# USBReallyTinyISPv1.net
KiCad netlist of a schematic drawn in EAGLE
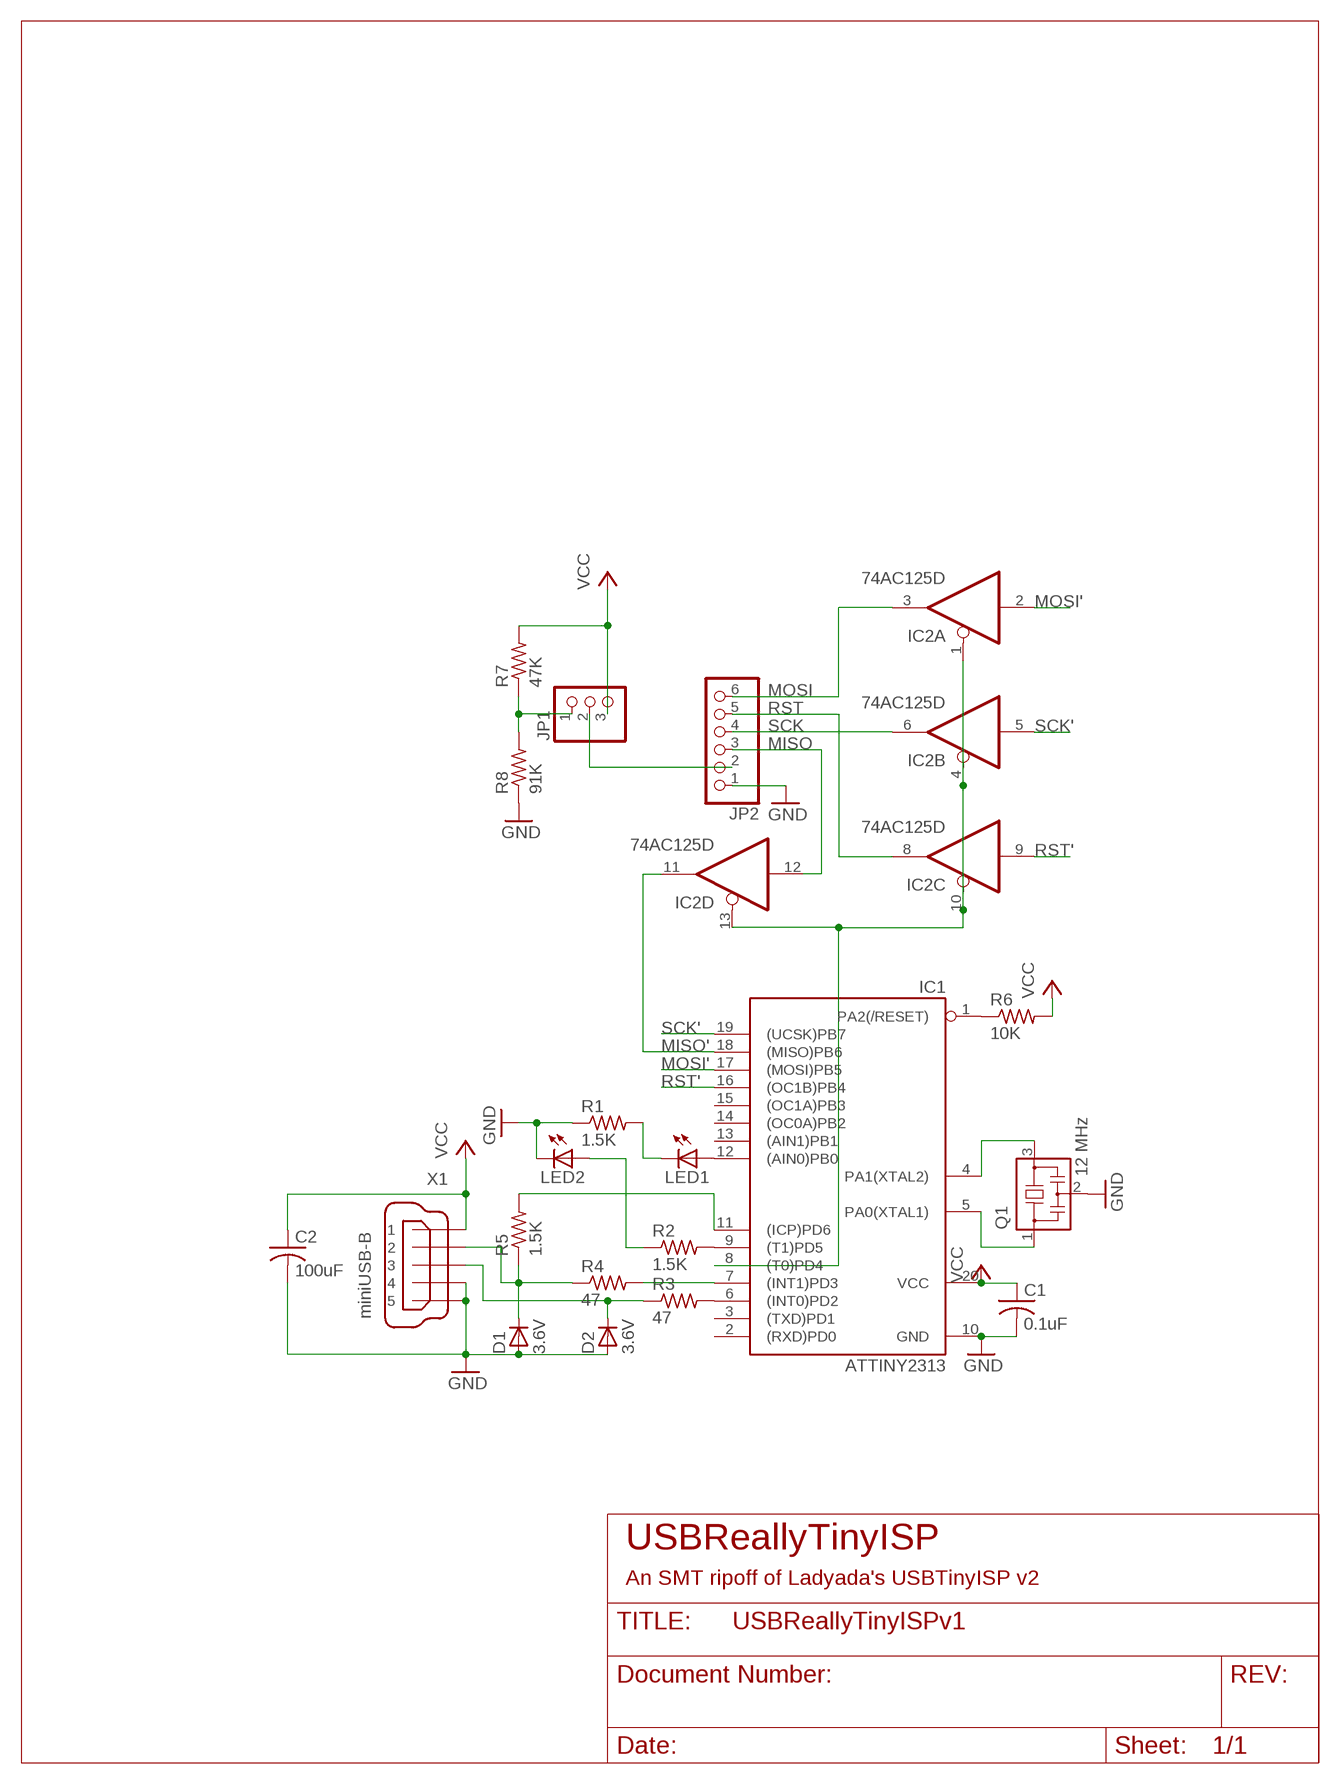
[diagram p0: schematic, sheet 1]

(export (version "E")
  (design (tool "Eeschema 10.0.6"))
  (components
    (comp (ref "C1")
      (value "0.1uF")
      (footprint "eagle-import:C0805")
      (libsource (lib "eagle-import") (part "C-USC0805"))
    )
    (comp (ref "C2")
      (value "100uF")
      (footprint "eagle-import:C1206")
      (libsource (lib "eagle-import") (part "resistor_C-USC1206"))
    )
    (comp (ref "D1")
      (value "3.6V")
      (footprint "eagle-import:SOD3718X135N")
      (libsource (lib "eagle-import") (part "DIODE_SOD-123"))
    )
    (comp (ref "D2")
      (value "3.6V")
      (footprint "eagle-import:SOD3718X135N")
      (libsource (lib "eagle-import") (part "DIODE_SOD-123"))
    )
    (comp (ref "IC1")
      (value "ATTINY2313")
      (footprint "eagle-import:SO20L$")
      (libsource (lib "eagle-import") (part "TINY2313-S"))
    )
    (comp (ref "IC2")
      (value "74AC125D")
      (footprint "eagle-import:SO14")
      (libsource (lib "eagle-import") (part "74125DAC"))
    )
    (comp (ref "JP1")
      (value "PINHD-1X3")
      (footprint "eagle-import:1X03")
      (libsource (lib "eagle-import") (part "PINHD-1X3"))
    )
    (comp (ref "JP2")
      (value "PINHD-1X6")
      (footprint "eagle-import:1X06")
      (libsource (lib "eagle-import") (part "PINHD-1X6"))
    )
    (comp (ref "LED1")
      (value "LEDSML0805")
      (footprint "eagle-import:SML0805")
      (libsource (lib "eagle-import") (part "LEDSML0805"))
    )
    (comp (ref "LED2")
      (value "LEDSML0805")
      (footprint "eagle-import:SML0805")
      (libsource (lib "eagle-import") (part "LEDSML0805"))
    )
    (comp (ref "Q1")
      (value "12 MHz")
      (footprint "eagle-import:CSTCR6M")
      (fields (field (name "MPN") "CSTCR6M00G53-R0"))
      (libsource (lib "eagle-import") (part "CSTCR6M00G53Z"))
    )
    (comp (ref "R1")
      (value "1.5K")
      (footprint "eagle-import:R0805")
      (libsource (lib "eagle-import") (part "R-US_R0805"))
    )
    (comp (ref "R2")
      (value "1.5K")
      (footprint "eagle-import:R0805")
      (libsource (lib "eagle-import") (part "R-US_R0805"))
    )
    (comp (ref "R3")
      (value "47")
      (footprint "eagle-import:R0805")
      (libsource (lib "eagle-import") (part "R-US_R0805"))
    )
    (comp (ref "R4")
      (value "47")
      (footprint "eagle-import:R0805")
      (libsource (lib "eagle-import") (part "R-US_R0805"))
    )
    (comp (ref "R5")
      (value "1.5K")
      (footprint "eagle-import:R0805")
      (libsource (lib "eagle-import") (part "R-US_R0805"))
    )
    (comp (ref "R6")
      (value "10K")
      (footprint "eagle-import:R0805")
      (libsource (lib "eagle-import") (part "R-US_R0805"))
    )
    (comp (ref "R7")
      (value "47K")
      (footprint "eagle-import:R0805")
      (libsource (lib "eagle-import") (part "R-US_R0805"))
    )
    (comp (ref "R8")
      (value "91K")
      (footprint "eagle-import:R0805")
      (libsource (lib "eagle-import") (part "R-US_R0805"))
    )
    (comp (ref "X1")
      (value "miniUSB-B")
      (footprint "eagle-import:UX60A-MB-5ST")
      (libsource (lib "eagle-import") (part "MINI-USB-UX60A-MB-5ST"))
    )
  )
  (nets
    (net (code "1") (name "/MISO") (class "Default")
      (node (ref "IC2") (pin "12") (pinfunction "I_12") (pintype "input"))
      (node (ref "JP2") (pin "3") (pinfunction "3_3") (pintype "passive"))
    )
    (net (code "2") (name "/MISO'") (class "Default")
      (node (ref "IC1") (pin "18") (pinfunction "(MISO)PB6_18") (pintype "bidirectional"))
      (node (ref "IC2") (pin "11") (pinfunction "O_11") (pintype "tri_state"))
    )
    (net (code "3") (name "/MOSI") (class "Default")
      (node (ref "IC2") (pin "3") (pinfunction "O_3") (pintype "tri_state"))
      (node (ref "JP2") (pin "6") (pinfunction "6_6") (pintype "passive"))
    )
    (net (code "4") (name "/MOSI'") (class "Default")
      (node (ref "IC1") (pin "17") (pinfunction "(MOSI)PB5_17") (pintype "bidirectional"))
      (node (ref "IC2") (pin "2") (pinfunction "I_2") (pintype "input"))
    )
    (net (code "5") (name "/RST") (class "Default")
      (node (ref "IC2") (pin "8") (pinfunction "O_8") (pintype "tri_state"))
      (node (ref "JP2") (pin "5") (pinfunction "5_5") (pintype "passive"))
    )
    (net (code "6") (name "/RST'") (class "Default")
      (node (ref "IC1") (pin "16") (pinfunction "(OC1B)PB4_16") (pintype "bidirectional"))
      (node (ref "IC2") (pin "9") (pinfunction "I_9") (pintype "input"))
    )
    (net (code "7") (name "/SCK") (class "Default")
      (node (ref "IC2") (pin "6") (pinfunction "O_6") (pintype "tri_state"))
      (node (ref "JP2") (pin "4") (pinfunction "4_4") (pintype "passive"))
    )
    (net (code "8") (name "/SCK'") (class "Default")
      (node (ref "IC1") (pin "19") (pinfunction "(UCSK)PB7_19") (pintype "bidirectional"))
      (node (ref "IC2") (pin "5") (pinfunction "I_5") (pintype "input"))
    )
    (net (code "9") (name "GND") (class "Default")
      (node (ref "C1") (pin "2") (pinfunction "2_2") (pintype "passive"))
      (node (ref "C2") (pin "2") (pinfunction "2_2") (pintype "passive"))
      (node (ref "D1") (pin "A") (pinfunction "A_A") (pintype "passive"))
      (node (ref "D2") (pin "A") (pinfunction "A_A") (pintype "passive"))
      (node (ref "IC1") (pin "10") (pinfunction "GND_10") (pintype "power_in"))
      (node (ref "JP2") (pin "1") (pinfunction "1_1") (pintype "passive"))
      (node (ref "LED2") (pin "C") (pinfunction "C_C") (pintype "passive"))
      (node (ref "Q1") (pin "2") (pinfunction "2_2") (pintype "passive"))
      (node (ref "R1") (pin "1") (pinfunction "1_1") (pintype "passive"))
      (node (ref "R8") (pin "1") (pinfunction "1_1") (pintype "passive"))
      (node (ref "X1") (pin "4") (pinfunction "4_4") (pintype "input"))
      (node (ref "X1") (pin "5") (pinfunction "5_5") (pintype "input"))
    )
    (net (code "10") (name "Net-(D1-PadK)") (class "Default")
      (node (ref "D1") (pin "K") (pinfunction "K_K") (pintype "passive"))
      (node (ref "R4") (pin "1") (pinfunction "1_1") (pintype "passive"))
      (node (ref "R5") (pin "1") (pinfunction "1_1") (pintype "passive"))
      (node (ref "X1") (pin "2") (pinfunction "2_2") (pintype "input"))
    )
    (net (code "11") (name "Net-(D2-PadK)") (class "Default")
      (node (ref "D2") (pin "K") (pinfunction "K_K") (pintype "passive"))
      (node (ref "R3") (pin "1") (pinfunction "1_1") (pintype "passive"))
      (node (ref "X1") (pin "3") (pinfunction "3_3") (pintype "input"))
    )
    (net (code "12") (name "Net-(IC1-(AIN0)PB0)") (class "Default")
      (node (ref "IC1") (pin "12") (pinfunction "(AIN0)PB0_12") (pintype "bidirectional"))
      (node (ref "LED1") (pin "A") (pinfunction "A_A") (pintype "passive"))
    )
    (net (code "13") (name "Net-(IC1-(ICP)PD6)") (class "Default")
      (node (ref "IC1") (pin "11") (pinfunction "(ICP)PD6_11") (pintype "bidirectional"))
      (node (ref "R5") (pin "2") (pinfunction "2_2") (pintype "passive"))
    )
    (net (code "14") (name "Net-(IC1-(INT0)PD2)") (class "Default")
      (node (ref "IC1") (pin "6") (pinfunction "(INT0)PD2_6") (pintype "bidirectional"))
      (node (ref "R3") (pin "2") (pinfunction "2_2") (pintype "passive"))
    )
    (net (code "15") (name "Net-(IC1-(INT1)PD3)") (class "Default")
      (node (ref "IC1") (pin "7") (pinfunction "(INT1)PD3_7") (pintype "bidirectional"))
      (node (ref "R4") (pin "2") (pinfunction "2_2") (pintype "passive"))
    )
    (net (code "16") (name "Net-(IC1-(T0)PD4)") (class "Default")
      (node (ref "IC1") (pin "8") (pinfunction "(T0)PD4_8") (pintype "bidirectional"))
      (node (ref "IC2") (pin "1") (pinfunction "OE_1") (pintype "input"))
      (node (ref "IC2") (pin "10") (pinfunction "OE_10") (pintype "input"))
      (node (ref "IC2") (pin "13") (pinfunction "OE_13") (pintype "input"))
      (node (ref "IC2") (pin "4") (pinfunction "OE_4") (pintype "input"))
    )
    (net (code "17") (name "Net-(IC1-(T1)PD5)") (class "Default")
      (node (ref "IC1") (pin "9") (pinfunction "(T1)PD5_9") (pintype "bidirectional"))
      (node (ref "R2") (pin "2") (pinfunction "2_2") (pintype "passive"))
    )
    (net (code "18") (name "Net-(IC1-PA0(XTAL1))") (class "Default")
      (node (ref "IC1") (pin "5") (pinfunction "PA0(XTAL1)_5") (pintype "bidirectional"))
      (node (ref "Q1") (pin "1") (pinfunction "1_1") (pintype "passive"))
    )
    (net (code "19") (name "Net-(IC1-PA1(XTAL2))") (class "Default")
      (node (ref "IC1") (pin "4") (pinfunction "PA1(XTAL2)_4") (pintype "bidirectional"))
      (node (ref "Q1") (pin "3") (pinfunction "3_3") (pintype "passive"))
    )
    (net (code "20") (name "Net-(IC1-PA2({slash}RESET))") (class "Default")
      (node (ref "IC1") (pin "1") (pinfunction "PA2(/RESET)_1") (pintype "input"))
      (node (ref "R6") (pin "1") (pinfunction "1_1") (pintype "passive"))
    )
    (net (code "21") (name "Net-(JP1-Pad1)") (class "Default")
      (node (ref "JP1") (pin "1") (pinfunction "1_1") (pintype "passive"))
      (node (ref "R7") (pin "1") (pinfunction "1_1") (pintype "passive"))
      (node (ref "R8") (pin "2") (pinfunction "2_2") (pintype "passive"))
    )
    (net (code "22") (name "Net-(JP1-Pad2)") (class "Default")
      (node (ref "JP1") (pin "2") (pinfunction "2_2") (pintype "passive"))
      (node (ref "JP2") (pin "2") (pinfunction "2_2") (pintype "passive"))
    )
    (net (code "23") (name "Net-(LED1-PadC)") (class "Default")
      (node (ref "LED1") (pin "C") (pinfunction "C_C") (pintype "passive"))
      (node (ref "R1") (pin "2") (pinfunction "2_2") (pintype "passive"))
    )
    (net (code "24") (name "Net-(LED2-PadA)") (class "Default")
      (node (ref "LED2") (pin "A") (pinfunction "A_A") (pintype "passive"))
      (node (ref "R2") (pin "1") (pinfunction "1_1") (pintype "passive"))
    )
    (net (code "25") (name "VCC") (class "Default")
      (node (ref "C1") (pin "1") (pinfunction "1_1") (pintype "passive"))
      (node (ref "C2") (pin "1") (pinfunction "1_1") (pintype "passive"))
      (node (ref "IC1") (pin "20") (pinfunction "VCC_20") (pintype "power_in"))
      (node (ref "JP1") (pin "3") (pinfunction "3_3") (pintype "passive"))
      (node (ref "R6") (pin "2") (pinfunction "2_2") (pintype "passive"))
      (node (ref "R7") (pin "2") (pinfunction "2_2") (pintype "passive"))
      (node (ref "X1") (pin "1") (pinfunction "1_1") (pintype "input"))
    )
    (net (code "26") (name "unconnected-(IC1-(AIN1)PB1-Pad13)") (class "Default")
      (node (ref "IC1") (pin "13") (pinfunction "(AIN1)PB1_13") (pintype "bidirectional"))
    )
    (net (code "27") (name "unconnected-(IC1-(OC0A)PB2-Pad14)") (class "Default")
      (node (ref "IC1") (pin "14") (pinfunction "(OC0A)PB2_14") (pintype "bidirectional"))
    )
    (net (code "28") (name "unconnected-(IC1-(OC1A)PB3-Pad15)") (class "Default")
      (node (ref "IC1") (pin "15") (pinfunction "(OC1A)PB3_15") (pintype "bidirectional"))
    )
    (net (code "29") (name "unconnected-(IC1-(RXD)PD0-Pad2)") (class "Default")
      (node (ref "IC1") (pin "2") (pinfunction "(RXD)PD0_2") (pintype "bidirectional"))
    )
    (net (code "30") (name "unconnected-(IC1-(TXD)PD1-Pad3)") (class "Default")
      (node (ref "IC1") (pin "3") (pinfunction "(TXD)PD1_3") (pintype "bidirectional"))
    )
  )
)
